# MGC3130_Board.net
KiCad netlist of a schematic drawn in EAGLE
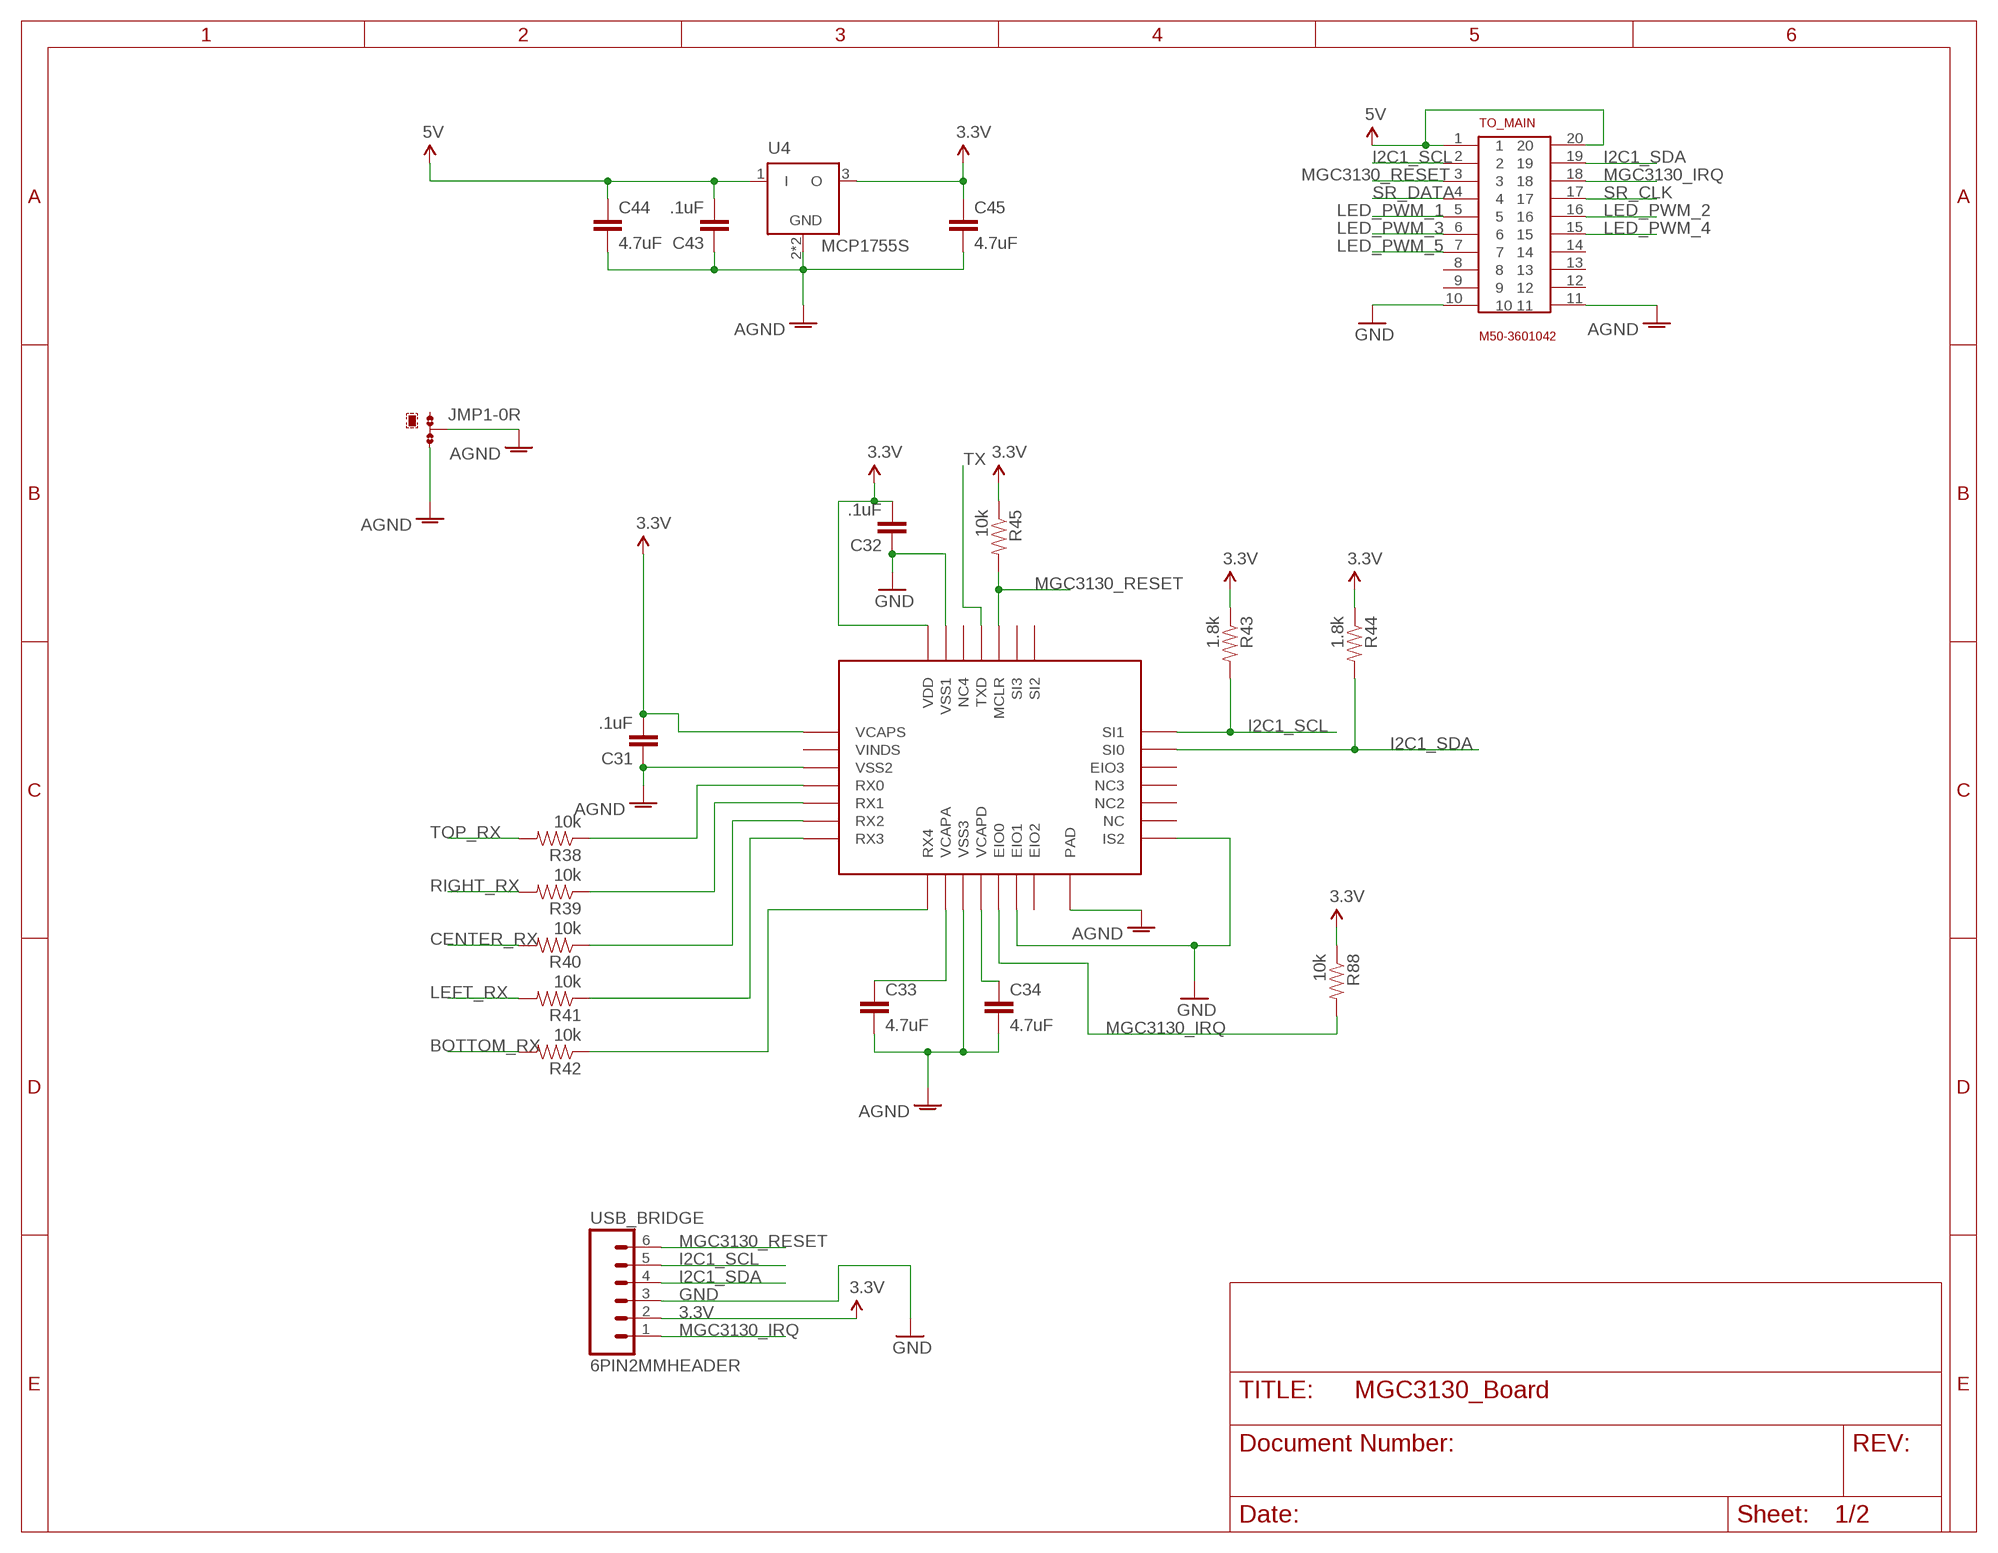
[diagram p0: schematic, sheet 1]
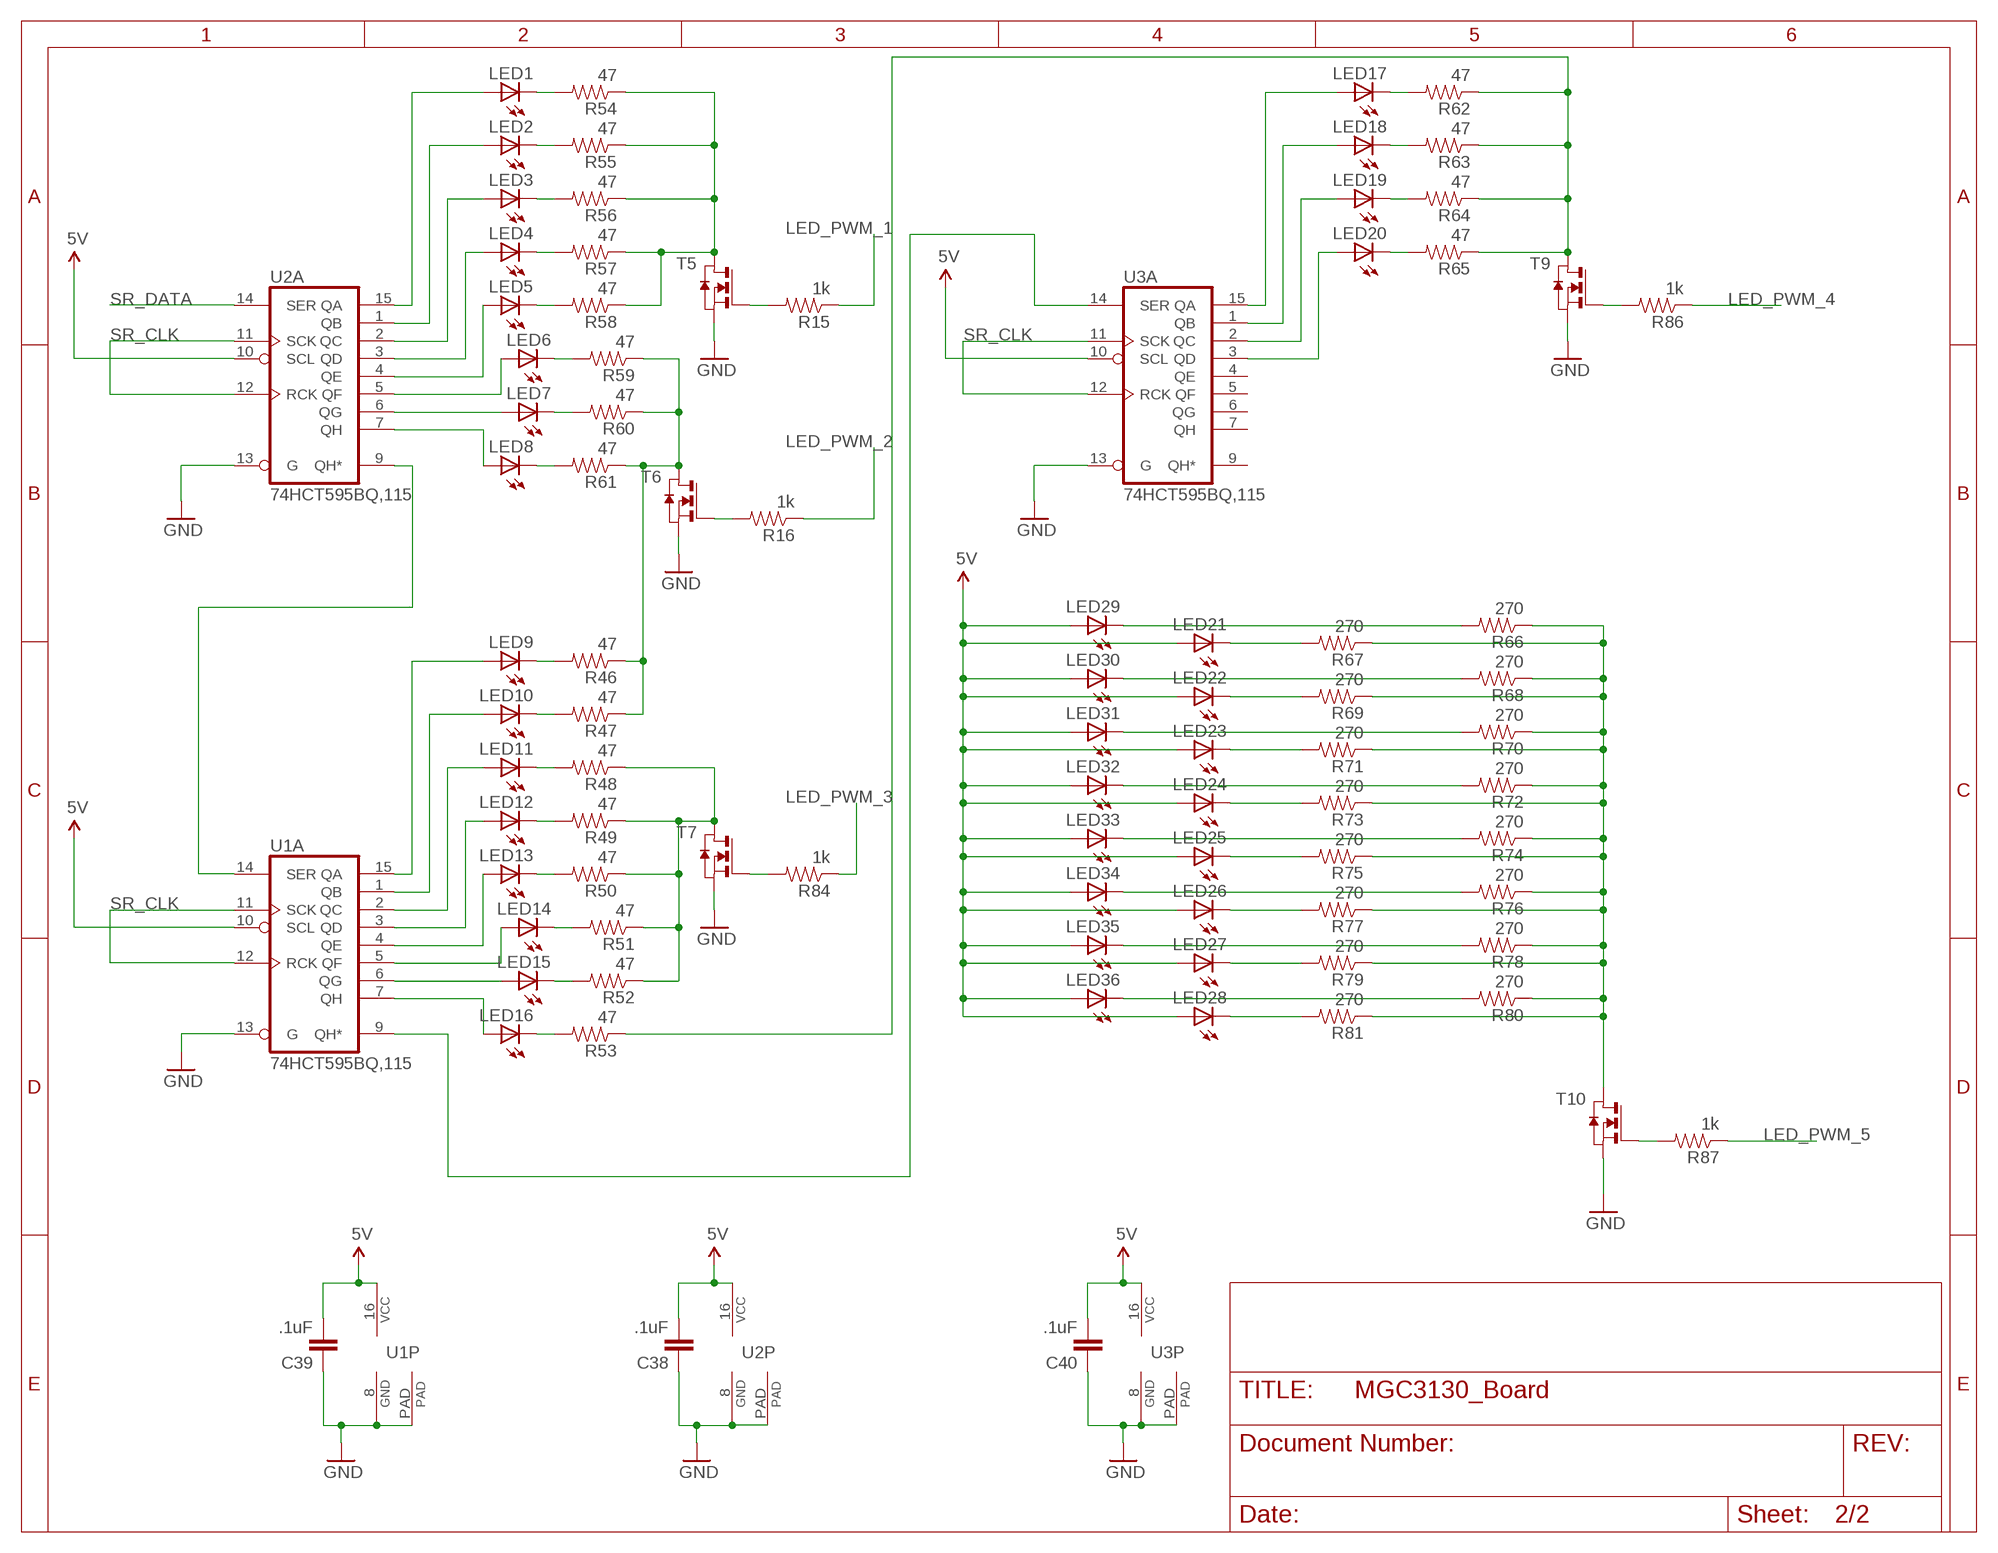
[diagram p1: schematic, sheet 2]

(export (version "E")
  (design (tool "Eeschema 10.0.6"))
  (components
    (comp (ref "C31")
      (value ".1uF")
      (footprint "eagle-import:0603-CAP")
      (libsource (lib "eagle-import") (part "SparkFun-Passives_CAP0603-CAP"))
    )
    (comp (ref "C32")
      (value ".1uF")
      (footprint "eagle-import:0603-CAP")
      (libsource (lib "eagle-import") (part "SparkFun-Passives_CAP0603-CAP"))
    )
    (comp (ref "C33")
      (value "4.7uF")
      (footprint "eagle-import:1206")
      (libsource (lib "eagle-import") (part "CAP1206"))
    )
    (comp (ref "C34")
      (value "4.7uF")
      (footprint "eagle-import:1206")
      (libsource (lib "eagle-import") (part "CAP1206"))
    )
    (comp (ref "C43")
      (value ".1uF")
      (footprint "eagle-import:0603-CAP")
      (libsource (lib "eagle-import") (part "SparkFun-Passives_CAP0603-CAP"))
    )
    (comp (ref "C44")
      (value "4.7uF")
      (footprint "eagle-import:1206")
      (libsource (lib "eagle-import") (part "CAP1206"))
    )
    (comp (ref "C45")
      (value "4.7uF")
      (footprint "eagle-import:1206")
      (libsource (lib "eagle-import") (part "CAP1206"))
    )
    (comp (ref "JMP1")
      (value "0R-JUMPA")
      (footprint "eagle-import:A0R-JMP")
      (libsource (lib "eagle-import") (part "0R-JUMPA"))
    )
    (comp (ref "R38")
      (value "10k")
      (footprint "eagle-import:0603-RES")
      (libsource (lib "eagle-import") (part "RESISTOR0603-RES"))
    )
    (comp (ref "R39")
      (value "10k")
      (footprint "eagle-import:0603-RES")
      (libsource (lib "eagle-import") (part "RESISTOR0603-RES"))
    )
    (comp (ref "R40")
      (value "10k")
      (footprint "eagle-import:0603-RES")
      (libsource (lib "eagle-import") (part "RESISTOR0603-RES"))
    )
    (comp (ref "R41")
      (value "10k")
      (footprint "eagle-import:0603-RES")
      (libsource (lib "eagle-import") (part "RESISTOR0603-RES"))
    )
    (comp (ref "R42")
      (value "10k")
      (footprint "eagle-import:0603-RES")
      (libsource (lib "eagle-import") (part "RESISTOR0603-RES"))
    )
    (comp (ref "R43")
      (value "1.8k")
      (footprint "eagle-import:0603-RES")
      (libsource (lib "eagle-import") (part "RESISTOR0603-RES"))
    )
    (comp (ref "R44")
      (value "1.8k")
      (footprint "eagle-import:0603-RES")
      (libsource (lib "eagle-import") (part "RESISTOR0603-RES"))
    )
    (comp (ref "R45")
      (value "10k")
      (footprint "eagle-import:0603-RES")
      (libsource (lib "eagle-import") (part "RESISTOR0603-RES"))
    )
    (comp (ref "R88")
      (value "10k")
      (footprint "eagle-import:0603-RES")
      (libsource (lib "eagle-import") (part "RESISTOR0603-RES"))
    )
    (comp (ref "TO_MAIN")
      (value "M50-3601042")
      (footprint "eagle-import:M50-3601042")
      (libsource (lib "eagle-import") (part "M50-3601042"))
    )
    (comp (ref "U4")
      (value "MCP1755S")
      (footprint "eagle-import:SOT223")
      (libsource (lib "eagle-import") (part "MCP1755S"))
    )
    (comp (ref "U14")
      (value "MGC3130")
      (footprint "eagle-import:QFN28")
      (libsource (lib "eagle-import") (part "MGC3130"))
    )
    (comp (ref "USB_BRIDGE")
      (value "6PIN2MMHEADER")
      (footprint "eagle-import:1X06_SMD_STRAIGHT")
      (libsource (lib "eagle-import") (part "6PIN2MMHEADER"))
    )
    (comp (ref "C38")
      (value ".1uF")
      (footprint "eagle-import:0603-CAP")
      (libsource (lib "eagle-import") (part "SparkFun-Passives_CAP0603-CAP"))
    )
    (comp (ref "C39")
      (value ".1uF")
      (footprint "eagle-import:0603-CAP")
      (libsource (lib "eagle-import") (part "SparkFun-Passives_CAP0603-CAP"))
    )
    (comp (ref "C40")
      (value ".1uF")
      (footprint "eagle-import:0603-CAP")
      (libsource (lib "eagle-import") (part "SparkFun-Passives_CAP0603-CAP"))
    )
    (comp (ref "LED1")
      (value "APA3010QBC/D-GX")
      (footprint "eagle-import:APA3010")
      (libsource (lib "eagle-import") (part "APA3010QBC/D-GX"))
    )
    (comp (ref "LED2")
      (value "APA3010QBC/D-GX")
      (footprint "eagle-import:APA3010")
      (libsource (lib "eagle-import") (part "APA3010QBC/D-GX"))
    )
    (comp (ref "LED3")
      (value "APA3010QBC/D-GX")
      (footprint "eagle-import:APA3010")
      (libsource (lib "eagle-import") (part "APA3010QBC/D-GX"))
    )
    (comp (ref "LED4")
      (value "APA3010QBC/D-GX")
      (footprint "eagle-import:APA3010")
      (libsource (lib "eagle-import") (part "APA3010QBC/D-GX"))
    )
    (comp (ref "LED5")
      (value "APA3010QBC/D-GX")
      (footprint "eagle-import:APA3010")
      (libsource (lib "eagle-import") (part "APA3010QBC/D-GX"))
    )
    (comp (ref "LED6")
      (value "APA3010QBC/D-GX")
      (footprint "eagle-import:APA3010")
      (libsource (lib "eagle-import") (part "APA3010QBC/D-GX"))
    )
    (comp (ref "LED7")
      (value "APA3010QBC/D-GX")
      (footprint "eagle-import:APA3010")
      (libsource (lib "eagle-import") (part "APA3010QBC/D-GX"))
    )
    (comp (ref "LED8")
      (value "APA3010QBC/D-GX")
      (footprint "eagle-import:APA3010")
      (libsource (lib "eagle-import") (part "APA3010QBC/D-GX"))
    )
    (comp (ref "LED9")
      (value "APA3010QBC/D-GX")
      (footprint "eagle-import:APA3010")
      (libsource (lib "eagle-import") (part "APA3010QBC/D-GX"))
    )
    (comp (ref "LED10")
      (value "APA3010QBC/D-GX")
      (footprint "eagle-import:APA3010")
      (libsource (lib "eagle-import") (part "APA3010QBC/D-GX"))
    )
    (comp (ref "LED11")
      (value "APA3010QBC/D-GX")
      (footprint "eagle-import:APA3010")
      (libsource (lib "eagle-import") (part "APA3010QBC/D-GX"))
    )
    (comp (ref "LED12")
      (value "APA3010QBC/D-GX")
      (footprint "eagle-import:APA3010")
      (libsource (lib "eagle-import") (part "APA3010QBC/D-GX"))
    )
    (comp (ref "LED13")
      (value "APA3010QBC/D-GX")
      (footprint "eagle-import:APA3010")
      (libsource (lib "eagle-import") (part "APA3010QBC/D-GX"))
    )
    (comp (ref "LED14")
      (value "APA3010QBC/D-GX")
      (footprint "eagle-import:APA3010")
      (libsource (lib "eagle-import") (part "APA3010QBC/D-GX"))
    )
    (comp (ref "LED15")
      (value "APA3010QBC/D-GX")
      (footprint "eagle-import:APA3010")
      (libsource (lib "eagle-import") (part "APA3010QBC/D-GX"))
    )
    (comp (ref "LED16")
      (value "APA3010QBC/D-GX")
      (footprint "eagle-import:APA3010")
      (libsource (lib "eagle-import") (part "APA3010QBC/D-GX"))
    )
    (comp (ref "LED17")
      (value "APA3010QBC/D-GX")
      (footprint "eagle-import:APA3010")
      (libsource (lib "eagle-import") (part "APA3010QBC/D-GX"))
    )
    (comp (ref "LED18")
      (value "APA3010QBC/D-GX")
      (footprint "eagle-import:APA3010")
      (libsource (lib "eagle-import") (part "APA3010QBC/D-GX"))
    )
    (comp (ref "LED19")
      (value "APA3010QBC/D-GX")
      (footprint "eagle-import:APA3010")
      (libsource (lib "eagle-import") (part "APA3010QBC/D-GX"))
    )
    (comp (ref "LED20")
      (value "APA3010QBC/D-GX")
      (footprint "eagle-import:APA3010")
      (libsource (lib "eagle-import") (part "APA3010QBC/D-GX"))
    )
    (comp (ref "LED21")
      (value "APA3010SRCPRV-GX")
      (footprint "eagle-import:APA3010")
      (libsource (lib "eagle-import") (part "APA3010SRCPRV-GX"))
    )
    (comp (ref "LED22")
      (value "APA3010SRCPRV-GX")
      (footprint "eagle-import:APA3010")
      (libsource (lib "eagle-import") (part "APA3010SRCPRV-GX"))
    )
    (comp (ref "LED23")
      (value "APA3010SRCPRV-GX")
      (footprint "eagle-import:APA3010")
      (libsource (lib "eagle-import") (part "APA3010SRCPRV-GX"))
    )
    (comp (ref "LED24")
      (value "APA3010SRCPRV-GX")
      (footprint "eagle-import:APA3010")
      (libsource (lib "eagle-import") (part "APA3010SRCPRV-GX"))
    )
    (comp (ref "LED25")
      (value "APA3010SRCPRV-GX")
      (footprint "eagle-import:APA3010")
      (libsource (lib "eagle-import") (part "APA3010SRCPRV-GX"))
    )
    (comp (ref "LED26")
      (value "APA3010SRCPRV-GX")
      (footprint "eagle-import:APA3010")
      (libsource (lib "eagle-import") (part "APA3010SRCPRV-GX"))
    )
    (comp (ref "LED27")
      (value "APA3010SRCPRV-GX")
      (footprint "eagle-import:APA3010")
      (libsource (lib "eagle-import") (part "APA3010SRCPRV-GX"))
    )
    (comp (ref "LED28")
      (value "APA3010SRCPRV-GX")
      (footprint "eagle-import:APA3010")
      (libsource (lib "eagle-import") (part "APA3010SRCPRV-GX"))
    )
    (comp (ref "LED29")
      (value "APA3010SRCPRV-GX")
      (footprint "eagle-import:APA3010")
      (libsource (lib "eagle-import") (part "APA3010SRCPRV-GX"))
    )
    (comp (ref "LED30")
      (value "APA3010SRCPRV-GX")
      (footprint "eagle-import:APA3010")
      (libsource (lib "eagle-import") (part "APA3010SRCPRV-GX"))
    )
    (comp (ref "LED31")
      (value "APA3010SRCPRV-GX")
      (footprint "eagle-import:APA3010")
      (libsource (lib "eagle-import") (part "APA3010SRCPRV-GX"))
    )
    (comp (ref "LED32")
      (value "APA3010SRCPRV-GX")
      (footprint "eagle-import:APA3010")
      (libsource (lib "eagle-import") (part "APA3010SRCPRV-GX"))
    )
    (comp (ref "LED33")
      (value "APA3010SRCPRV-GX")
      (footprint "eagle-import:APA3010")
      (libsource (lib "eagle-import") (part "APA3010SRCPRV-GX"))
    )
    (comp (ref "LED34")
      (value "APA3010SRCPRV-GX")
      (footprint "eagle-import:APA3010")
      (libsource (lib "eagle-import") (part "APA3010SRCPRV-GX"))
    )
    (comp (ref "LED35")
      (value "APA3010SRCPRV-GX")
      (footprint "eagle-import:APA3010")
      (libsource (lib "eagle-import") (part "APA3010SRCPRV-GX"))
    )
    (comp (ref "LED36")
      (value "APA3010SRCPRV-GX")
      (footprint "eagle-import:APA3010")
      (libsource (lib "eagle-import") (part "APA3010SRCPRV-GX"))
    )
    (comp (ref "R15")
      (value "1k")
      (footprint "eagle-import:0603-RES")
      (libsource (lib "eagle-import") (part "RESISTOR0603-RES"))
    )
    (comp (ref "R16")
      (value "1k")
      (footprint "eagle-import:0603-RES")
      (libsource (lib "eagle-import") (part "RESISTOR0603-RES"))
    )
    (comp (ref "R46")
      (value "47")
      (footprint "eagle-import:0603-RES")
      (libsource (lib "eagle-import") (part "RESISTOR0603-RES"))
    )
    (comp (ref "R47")
      (value "47")
      (footprint "eagle-import:0603-RES")
      (libsource (lib "eagle-import") (part "RESISTOR0603-RES"))
    )
    (comp (ref "R48")
      (value "47")
      (footprint "eagle-import:0603-RES")
      (libsource (lib "eagle-import") (part "RESISTOR0603-RES"))
    )
    (comp (ref "R49")
      (value "47")
      (footprint "eagle-import:0603-RES")
      (libsource (lib "eagle-import") (part "RESISTOR0603-RES"))
    )
    (comp (ref "R50")
      (value "47")
      (footprint "eagle-import:0603-RES")
      (libsource (lib "eagle-import") (part "RESISTOR0603-RES"))
    )
    (comp (ref "R51")
      (value "47")
      (footprint "eagle-import:0603-RES")
      (libsource (lib "eagle-import") (part "RESISTOR0603-RES"))
    )
    (comp (ref "R52")
      (value "47")
      (footprint "eagle-import:0603-RES")
      (libsource (lib "eagle-import") (part "RESISTOR0603-RES"))
    )
    (comp (ref "R53")
      (value "47")
      (footprint "eagle-import:0603-RES")
      (libsource (lib "eagle-import") (part "RESISTOR0603-RES"))
    )
    (comp (ref "R54")
      (value "47")
      (footprint "eagle-import:0603-RES")
      (libsource (lib "eagle-import") (part "RESISTOR0603-RES"))
    )
    (comp (ref "R55")
      (value "47")
      (footprint "eagle-import:0603-RES")
      (libsource (lib "eagle-import") (part "RESISTOR0603-RES"))
    )
    (comp (ref "R56")
      (value "47")
      (footprint "eagle-import:0603-RES")
      (libsource (lib "eagle-import") (part "RESISTOR0603-RES"))
    )
    (comp (ref "R57")
      (value "47")
      (footprint "eagle-import:0603-RES")
      (libsource (lib "eagle-import") (part "RESISTOR0603-RES"))
    )
    (comp (ref "R58")
      (value "47")
      (footprint "eagle-import:0603-RES")
      (libsource (lib "eagle-import") (part "RESISTOR0603-RES"))
    )
    (comp (ref "R59")
      (value "47")
      (footprint "eagle-import:0603-RES")
      (libsource (lib "eagle-import") (part "RESISTOR0603-RES"))
    )
    (comp (ref "R60")
      (value "47")
      (footprint "eagle-import:0603-RES")
      (libsource (lib "eagle-import") (part "RESISTOR0603-RES"))
    )
    (comp (ref "R61")
      (value "47")
      (footprint "eagle-import:0603-RES")
      (libsource (lib "eagle-import") (part "RESISTOR0603-RES"))
    )
    (comp (ref "R62")
      (value "47")
      (footprint "eagle-import:0603-RES")
      (libsource (lib "eagle-import") (part "RESISTOR0603-RES"))
    )
    (comp (ref "R63")
      (value "47")
      (footprint "eagle-import:0603-RES")
      (libsource (lib "eagle-import") (part "RESISTOR0603-RES"))
    )
    (comp (ref "R64")
      (value "47")
      (footprint "eagle-import:0603-RES")
      (libsource (lib "eagle-import") (part "RESISTOR0603-RES"))
    )
    (comp (ref "R65")
      (value "47")
      (footprint "eagle-import:0603-RES")
      (libsource (lib "eagle-import") (part "RESISTOR0603-RES"))
    )
    (comp (ref "R66")
      (value "270")
      (footprint "eagle-import:0603-RES")
      (libsource (lib "eagle-import") (part "RESISTOR0603-RES"))
    )
    (comp (ref "R67")
      (value "270")
      (footprint "eagle-import:0603-RES")
      (libsource (lib "eagle-import") (part "RESISTOR0603-RES"))
    )
    (comp (ref "R68")
      (value "270")
      (footprint "eagle-import:0603-RES")
      (libsource (lib "eagle-import") (part "RESISTOR0603-RES"))
    )
    (comp (ref "R69")
      (value "270")
      (footprint "eagle-import:0603-RES")
      (libsource (lib "eagle-import") (part "RESISTOR0603-RES"))
    )
    (comp (ref "R70")
      (value "270")
      (footprint "eagle-import:0603-RES")
      (libsource (lib "eagle-import") (part "RESISTOR0603-RES"))
    )
    (comp (ref "R71")
      (value "270")
      (footprint "eagle-import:0603-RES")
      (libsource (lib "eagle-import") (part "RESISTOR0603-RES"))
    )
    (comp (ref "R72")
      (value "270")
      (footprint "eagle-import:0603-RES")
      (libsource (lib "eagle-import") (part "RESISTOR0603-RES"))
    )
    (comp (ref "R73")
      (value "270")
      (footprint "eagle-import:0603-RES")
      (libsource (lib "eagle-import") (part "RESISTOR0603-RES"))
    )
    (comp (ref "R74")
      (value "270")
      (footprint "eagle-import:0603-RES")
      (libsource (lib "eagle-import") (part "RESISTOR0603-RES"))
    )
    (comp (ref "R75")
      (value "270")
      (footprint "eagle-import:0603-RES")
      (libsource (lib "eagle-import") (part "RESISTOR0603-RES"))
    )
    (comp (ref "R76")
      (value "270")
      (footprint "eagle-import:0603-RES")
      (libsource (lib "eagle-import") (part "RESISTOR0603-RES"))
    )
    (comp (ref "R77")
      (value "270")
      (footprint "eagle-import:0603-RES")
      (libsource (lib "eagle-import") (part "RESISTOR0603-RES"))
    )
    (comp (ref "R78")
      (value "270")
      (footprint "eagle-import:0603-RES")
      (libsource (lib "eagle-import") (part "RESISTOR0603-RES"))
    )
    (comp (ref "R79")
      (value "270")
      (footprint "eagle-import:0603-RES")
      (libsource (lib "eagle-import") (part "RESISTOR0603-RES"))
    )
    (comp (ref "R80")
      (value "270")
      (footprint "eagle-import:0603-RES")
      (libsource (lib "eagle-import") (part "RESISTOR0603-RES"))
    )
    (comp (ref "R81")
      (value "270")
      (footprint "eagle-import:0603-RES")
      (libsource (lib "eagle-import") (part "RESISTOR0603-RES"))
    )
    (comp (ref "R84")
      (value "1k")
      (footprint "eagle-import:0603-RES")
      (libsource (lib "eagle-import") (part "RESISTOR0603-RES"))
    )
    (comp (ref "R86")
      (value "1k")
      (footprint "eagle-import:0603-RES")
      (libsource (lib "eagle-import") (part "RESISTOR0603-RES"))
    )
    (comp (ref "R87")
      (value "1k")
      (footprint "eagle-import:0603-RES")
      (libsource (lib "eagle-import") (part "RESISTOR0603-RES"))
    )
    (comp (ref "T5")
      (value "NMOSSOT23")
      (footprint "eagle-import:SOT-23")
      (libsource (lib "eagle-import") (part "NMOSSOT23"))
    )
    (comp (ref "T6")
      (value "NMOSSOT23")
      (footprint "eagle-import:SOT-23")
      (libsource (lib "eagle-import") (part "NMOSSOT23"))
    )
    (comp (ref "T7")
      (value "NMOSSOT23")
      (footprint "eagle-import:SOT-23")
      (libsource (lib "eagle-import") (part "NMOSSOT23"))
    )
    (comp (ref "T9")
      (value "NMOSSOT23")
      (footprint "eagle-import:SOT-23")
      (libsource (lib "eagle-import") (part "NMOSSOT23"))
    )
    (comp (ref "T10")
      (value "NMOSSOT23")
      (footprint "eagle-import:SOT-23")
      (libsource (lib "eagle-import") (part "NMOSSOT23"))
    )
    (comp (ref "U1")
      (value "74HCT595BQ,115")
      (footprint "eagle-import:DHVQFN16")
      (libsource (lib "eagle-import") (part "74HCT595BQ,115"))
    )
    (comp (ref "U2")
      (value "74HCT595BQ,115")
      (footprint "eagle-import:DHVQFN16")
      (libsource (lib "eagle-import") (part "74HCT595BQ,115"))
    )
    (comp (ref "U3")
      (value "74HCT595BQ,115")
      (footprint "eagle-import:DHVQFN16")
      (libsource (lib "eagle-import") (part "74HCT595BQ,115"))
    )
  )
  (nets
    (net (code "1") (name "3.3V") (class "Default")
      (node (ref "C31") (pin "2") (pinfunction "2_2") (pintype "passive"))
      (node (ref "C32") (pin "2") (pinfunction "2_2") (pintype "passive"))
      (node (ref "C45") (pin "1") (pinfunction "1_1") (pintype "passive"))
      (node (ref "R43") (pin "1") (pinfunction "1_1") (pintype "passive"))
      (node (ref "R44") (pin "1") (pinfunction "1_1") (pintype "passive"))
      (node (ref "R45") (pin "1") (pinfunction "1_1") (pintype "passive"))
      (node (ref "R88") (pin "1") (pinfunction "1_1") (pintype "passive"))
      (node (ref "U14") (pin "P$1") (pinfunction "VCAPS_P$1") (pintype "bidirectional"))
      (node (ref "U14") (pin "P$28") (pinfunction "VDD_P$28") (pintype "bidirectional"))
      (node (ref "U4") (pin "3") (pinfunction "O_3") (pintype "input"))
      (node (ref "USB_BRIDGE") (pin "2") (pinfunction "2_2") (pintype "passive"))
    )
    (net (code "2") (name "5V") (class "Default")
      (node (ref "C38") (pin "2") (pinfunction "2_2") (pintype "passive"))
      (node (ref "C39") (pin "2") (pinfunction "2_2") (pintype "passive"))
      (node (ref "C40") (pin "2") (pinfunction "2_2") (pintype "passive"))
      (node (ref "C43") (pin "2") (pinfunction "2_2") (pintype "passive"))
      (node (ref "C44") (pin "1") (pinfunction "1_1") (pintype "passive"))
      (node (ref "LED21") (pin "P$2") (pinfunction "A_P$2") (pintype "passive"))
      (node (ref "LED22") (pin "P$2") (pinfunction "A_P$2") (pintype "passive"))
      (node (ref "LED23") (pin "P$2") (pinfunction "A_P$2") (pintype "passive"))
      (node (ref "LED24") (pin "P$2") (pinfunction "A_P$2") (pintype "passive"))
      (node (ref "LED25") (pin "P$2") (pinfunction "A_P$2") (pintype "passive"))
      (node (ref "LED26") (pin "P$2") (pinfunction "A_P$2") (pintype "passive"))
      (node (ref "LED27") (pin "P$2") (pinfunction "A_P$2") (pintype "passive"))
      (node (ref "LED28") (pin "P$2") (pinfunction "A_P$2") (pintype "passive"))
      (node (ref "LED29") (pin "P$2") (pinfunction "A_P$2") (pintype "passive"))
      (node (ref "LED30") (pin "P$2") (pinfunction "A_P$2") (pintype "passive"))
      (node (ref "LED31") (pin "P$2") (pinfunction "A_P$2") (pintype "passive"))
      (node (ref "LED32") (pin "P$2") (pinfunction "A_P$2") (pintype "passive"))
      (node (ref "LED33") (pin "P$2") (pinfunction "A_P$2") (pintype "passive"))
      (node (ref "LED34") (pin "P$2") (pinfunction "A_P$2") (pintype "passive"))
      (node (ref "LED35") (pin "P$2") (pinfunction "A_P$2") (pintype "passive"))
      (node (ref "LED36") (pin "P$2") (pinfunction "A_P$2") (pintype "passive"))
      (node (ref "TO_MAIN") (pin "1") (pinfunction "1_1") (pintype "bidirectional"))
      (node (ref "TO_MAIN") (pin "20") (pinfunction "20_20") (pintype "bidirectional"))
      (node (ref "U1") (pin "10") (pinfunction "SCL_10") (pintype "input"))
      (node (ref "U1") (pin "16") (pinfunction "VCC_16") (pintype "power_in"))
      (node (ref "U2") (pin "10") (pinfunction "SCL_10") (pintype "input"))
      (node (ref "U2") (pin "16") (pinfunction "VCC_16") (pintype "power_in"))
      (node (ref "U3") (pin "10") (pinfunction "SCL_10") (pintype "input"))
      (node (ref "U3") (pin "16") (pinfunction "VCC_16") (pintype "power_in"))
      (node (ref "U4") (pin "1") (pinfunction "I_1") (pintype "input"))
    )
    (net (code "3") (name "AGND") (class "Default")
      (node (ref "C31") (pin "1") (pinfunction "1_1") (pintype "passive"))
      (node (ref "C33") (pin "2") (pinfunction "2_2") (pintype "passive"))
      (node (ref "C34") (pin "2") (pinfunction "2_2") (pintype "passive"))
      (node (ref "C43") (pin "1") (pinfunction "1_1") (pintype "passive"))
      (node (ref "C44") (pin "2") (pinfunction "2_2") (pintype "passive"))
      (node (ref "C45") (pin "2") (pinfunction "2_2") (pintype "passive"))
      (node (ref "JMP1") (pin "2") (pinfunction "2_2") (pintype "passive"))
      (node (ref "JMP1") (pin "3") (pinfunction "3_3") (pintype "passive"))
      (node (ref "TO_MAIN") (pin "11") (pinfunction "11_11") (pintype "bidirectional"))
      (node (ref "U14") (pin "P$10") (pinfunction "VSS3_P$10") (pintype "bidirectional"))
      (node (ref "U14") (pin "P$29") (pinfunction "PAD_P$29") (pintype "bidirectional"))
      (node (ref "U14") (pin "P$3") (pinfunction "VSS2_P$3") (pintype "bidirectional"))
      (node (ref "U4") (pin "2") (pinfunction "GND_2") (pintype "power_in"))
      (node (ref "U4") (pin "4") (pinfunction "GND_4") (pintype "power_in"))
    )
    (net (code "4") (name "BOTTOM_RX") (class "Default")
      (node (ref "R42") (pin "2") (pinfunction "2_2") (pintype "passive"))
    )
    (net (code "5") (name "CENTER_RX") (class "Default")
      (node (ref "R40") (pin "2") (pinfunction "2_2") (pintype "passive"))
    )
    (net (code "6") (name "GND") (class "Default")
      (node (ref "C32") (pin "1") (pinfunction "1_1") (pintype "passive"))
      (node (ref "C38") (pin "1") (pinfunction "1_1") (pintype "passive"))
      (node (ref "C39") (pin "1") (pinfunction "1_1") (pintype "passive"))
      (node (ref "C40") (pin "1") (pinfunction "1_1") (pintype "passive"))
      (node (ref "T10") (pin "2") (pinfunction "S_2") (pintype "passive"))
      (node (ref "T5") (pin "2") (pinfunction "S_2") (pintype "passive"))
      (node (ref "T6") (pin "2") (pinfunction "S_2") (pintype "passive"))
      (node (ref "T7") (pin "2") (pinfunction "S_2") (pintype "passive"))
      (node (ref "T9") (pin "2") (pinfunction "S_2") (pintype "passive"))
      (node (ref "TO_MAIN") (pin "10") (pinfunction "10_10") (pintype "bidirectional"))
      (node (ref "U1") (pin "13") (pinfunction "G_13") (pintype "input"))
      (node (ref "U1") (pin "8") (pinfunction "GND_8") (pintype "power_in"))
      (node (ref "U1") (pin "PAD") (pinfunction "GND1_PAD") (pintype "power_in"))
      (node (ref "U14") (pin "P$13") (pinfunction "EIO1_P$13") (pintype "bidirectional"))
      (node (ref "U14") (pin "P$15") (pinfunction "IS2_P$15") (pintype "bidirectional"))
      (node (ref "U14") (pin "P$27") (pinfunction "VSS1_P$27") (pintype "bidirectional"))
      (node (ref "U2") (pin "13") (pinfunction "G_13") (pintype "input"))
      (node (ref "U2") (pin "8") (pinfunction "GND_8") (pintype "power_in"))
      (node (ref "U2") (pin "PAD") (pinfunction "GND1_PAD") (pintype "power_in"))
      (node (ref "U3") (pin "13") (pinfunction "G_13") (pintype "input"))
      (node (ref "U3") (pin "8") (pinfunction "GND_8") (pintype "power_in"))
      (node (ref "U3") (pin "PAD") (pinfunction "GND1_PAD") (pintype "power_in"))
      (node (ref "USB_BRIDGE") (pin "3") (pinfunction "3_3") (pintype "passive"))
    )
    (net (code "7") (name "I2C1_SCL") (class "Default")
      (node (ref "R43") (pin "2") (pinfunction "2_2") (pintype "passive"))
      (node (ref "TO_MAIN") (pin "2") (pinfunction "2_2") (pintype "bidirectional"))
      (node (ref "U14") (pin "P$21") (pinfunction "SI1_P$21") (pintype "bidirectional"))
      (node (ref "USB_BRIDGE") (pin "5") (pinfunction "5_5") (pintype "passive"))
    )
    (net (code "8") (name "I2C1_SDA") (class "Default")
      (node (ref "R44") (pin "2") (pinfunction "2_2") (pintype "passive"))
      (node (ref "TO_MAIN") (pin "19") (pinfunction "19_19") (pintype "bidirectional"))
      (node (ref "U14") (pin "P$20") (pinfunction "SI0_P$20") (pintype "bidirectional"))
      (node (ref "USB_BRIDGE") (pin "4") (pinfunction "4_4") (pintype "passive"))
    )
    (net (code "9") (name "LED_PWM_1") (class "Default")
      (node (ref "R15") (pin "1") (pinfunction "1_1") (pintype "passive"))
      (node (ref "TO_MAIN") (pin "5") (pinfunction "5_5") (pintype "bidirectional"))
    )
    (net (code "10") (name "LED_PWM_2") (class "Default")
      (node (ref "R16") (pin "1") (pinfunction "1_1") (pintype "passive"))
      (node (ref "TO_MAIN") (pin "16") (pinfunction "16_16") (pintype "bidirectional"))
    )
    (net (code "11") (name "LED_PWM_3") (class "Default")
      (node (ref "R84") (pin "1") (pinfunction "1_1") (pintype "passive"))
      (node (ref "TO_MAIN") (pin "6") (pinfunction "6_6") (pintype "bidirectional"))
    )
    (net (code "12") (name "LED_PWM_4") (class "Default")
      (node (ref "R86") (pin "1") (pinfunction "1_1") (pintype "passive"))
      (node (ref "TO_MAIN") (pin "15") (pinfunction "15_15") (pintype "bidirectional"))
    )
    (net (code "13") (name "LED_PWM_5") (class "Default")
      (node (ref "R87") (pin "1") (pinfunction "1_1") (pintype "passive"))
      (node (ref "TO_MAIN") (pin "7") (pinfunction "7_7") (pintype "bidirectional"))
    )
    (net (code "14") (name "LEFT_RX") (class "Default")
      (node (ref "R41") (pin "2") (pinfunction "2_2") (pintype "passive"))
    )
    (net (code "15") (name "MGC3130_IRQ") (class "Default")
      (node (ref "R88") (pin "2") (pinfunction "2_2") (pintype "passive"))
      (node (ref "TO_MAIN") (pin "18") (pinfunction "18_18") (pintype "bidirectional"))
      (node (ref "U14") (pin "P$12") (pinfunction "EIO0_P$12") (pintype "bidirectional"))
      (node (ref "USB_BRIDGE") (pin "1") (pinfunction "1_1") (pintype "passive"))
    )
    (net (code "16") (name "MGC3130_RESET") (class "Default")
      (node (ref "R45") (pin "2") (pinfunction "2_2") (pintype "passive"))
      (node (ref "TO_MAIN") (pin "3") (pinfunction "3_3") (pintype "bidirectional"))
      (node (ref "U14") (pin "P$24") (pinfunction "MCLR_P$24") (pintype "bidirectional"))
      (node (ref "USB_BRIDGE") (pin "6") (pinfunction "6_6") (pintype "passive"))
    )
    (net (code "17") (name "Net-(LED1-A)") (class "Default")
      (node (ref "LED1") (pin "P$2") (pinfunction "A_P$2") (pintype "passive"))
      (node (ref "U2") (pin "15") (pinfunction "QA_15") (pintype "tri_state"))
    )
    (net (code "18") (name "Net-(LED1-C)") (class "Default")
      (node (ref "LED1") (pin "P$1") (pinfunction "C_P$1") (pintype "passive"))
      (node (ref "R54") (pin "2") (pinfunction "2_2") (pintype "passive"))
    )
    (net (code "19") (name "Net-(LED2-A)") (class "Default")
      (node (ref "LED2") (pin "P$2") (pinfunction "A_P$2") (pintype "passive"))
      (node (ref "U2") (pin "1") (pinfunction "QB_1") (pintype "tri_state"))
    )
    (net (code "20") (name "Net-(LED2-C)") (class "Default")
      (node (ref "LED2") (pin "P$1") (pinfunction "C_P$1") (pintype "passive"))
      (node (ref "R55") (pin "2") (pinfunction "2_2") (pintype "passive"))
    )
    (net (code "21") (name "Net-(LED3-A)") (class "Default")
      (node (ref "LED3") (pin "P$2") (pinfunction "A_P$2") (pintype "passive"))
      (node (ref "U2") (pin "2") (pinfunction "QC_2") (pintype "tri_state"))
    )
    (net (code "22") (name "Net-(LED3-C)") (class "Default")
      (node (ref "LED3") (pin "P$1") (pinfunction "C_P$1") (pintype "passive"))
      (node (ref "R56") (pin "2") (pinfunction "2_2") (pintype "passive"))
    )
    (net (code "23") (name "Net-(LED4-A)") (class "Default")
      (node (ref "LED4") (pin "P$2") (pinfunction "A_P$2") (pintype "passive"))
      (node (ref "U2") (pin "3") (pinfunction "QD_3") (pintype "tri_state"))
    )
    (net (code "24") (name "Net-(LED4-C)") (class "Default")
      (node (ref "LED4") (pin "P$1") (pinfunction "C_P$1") (pintype "passive"))
      (node (ref "R57") (pin "2") (pinfunction "2_2") (pintype "passive"))
    )
    (net (code "25") (name "Net-(LED5-A)") (class "Default")
      (node (ref "LED5") (pin "P$2") (pinfunction "A_P$2") (pintype "passive"))
      (node (ref "U2") (pin "4") (pinfunction "QE_4") (pintype "tri_state"))
    )
    (net (code "26") (name "Net-(LED5-C)") (class "Default")
      (node (ref "LED5") (pin "P$1") (pinfunction "C_P$1") (pintype "passive"))
      (node (ref "R58") (pin "2") (pinfunction "2_2") (pintype "passive"))
    )
    (net (code "27") (name "Net-(LED6-A)") (class "Default")
      (node (ref "LED6") (pin "P$2") (pinfunction "A_P$2") (pintype "passive"))
      (node (ref "U2") (pin "5") (pinfunction "QF_5") (pintype "tri_state"))
    )
    (net (code "28") (name "Net-(LED6-C)") (class "Default")
      (node (ref "LED6") (pin "P$1") (pinfunction "C_P$1") (pintype "passive"))
      (node (ref "R59") (pin "2") (pinfunction "2_2") (pintype "passive"))
    )
    (net (code "29") (name "Net-(LED7-A)") (class "Default")
      (node (ref "LED7") (pin "P$2") (pinfunction "A_P$2") (pintype "passive"))
      (node (ref "U2") (pin "6") (pinfunction "QG_6") (pintype "tri_state"))
    )
    (net (code "30") (name "Net-(LED7-C)") (class "Default")
      (node (ref "LED7") (pin "P$1") (pinfunction "C_P$1") (pintype "passive"))
      (node (ref "R60") (pin "2") (pinfunction "2_2") (pintype "passive"))
    )
    (net (code "31") (name "Net-(LED8-A)") (class "Default")
      (node (ref "LED8") (pin "P$2") (pinfunction "A_P$2") (pintype "passive"))
      (node (ref "U2") (pin "7") (pinfunction "QH_7") (pintype "tri_state"))
    )
    (net (code "32") (name "Net-(LED8-C)") (class "Default")
      (node (ref "LED8") (pin "P$1") (pinfunction "C_P$1") (pintype "passive"))
      (node (ref "R61") (pin "2") (pinfunction "2_2") (pintype "passive"))
    )
    (net (code "33") (name "Net-(LED9-A)") (class "Default")
      (node (ref "LED9") (pin "P$2") (pinfunction "A_P$2") (pintype "passive"))
      (node (ref "U1") (pin "15") (pinfunction "QA_15") (pintype "tri_state"))
    )
    (net (code "34") (name "Net-(LED9-C)") (class "Default")
      (node (ref "LED9") (pin "P$1") (pinfunction "C_P$1") (pintype "passive"))
      (node (ref "R46") (pin "2") (pinfunction "2_2") (pintype "passive"))
    )
    (net (code "35") (name "Net-(LED10-A)") (class "Default")
      (node (ref "LED10") (pin "P$2") (pinfunction "A_P$2") (pintype "passive"))
      (node (ref "U1") (pin "1") (pinfunction "QB_1") (pintype "tri_state"))
    )
    (net (code "36") (name "Net-(LED10-C)") (class "Default")
      (node (ref "LED10") (pin "P$1") (pinfunction "C_P$1") (pintype "passive"))
      (node (ref "R47") (pin "2") (pinfunction "2_2") (pintype "passive"))
    )
    (net (code "37") (name "Net-(LED11-A)") (class "Default")
      (node (ref "LED11") (pin "P$2") (pinfunction "A_P$2") (pintype "passive"))
      (node (ref "U1") (pin "2") (pinfunction "QC_2") (pintype "tri_state"))
    )
    (net (code "38") (name "Net-(LED11-C)") (class "Default")
      (node (ref "LED11") (pin "P$1") (pinfunction "C_P$1") (pintype "passive"))
      (node (ref "R48") (pin "2") (pinfunction "2_2") (pintype "passive"))
    )
    (net (code "39") (name "Net-(LED12-A)") (class "Default")
      (node (ref "LED12") (pin "P$2") (pinfunction "A_P$2") (pintype "passive"))
      (node (ref "U1") (pin "3") (pinfunction "QD_3") (pintype "tri_state"))
    )
    (net (code "40") (name "Net-(LED12-C)") (class "Default")
      (node (ref "LED12") (pin "P$1") (pinfunction "C_P$1") (pintype "passive"))
      (node (ref "R49") (pin "2") (pinfunction "2_2") (pintype "passive"))
    )
    (net (code "41") (name "Net-(LED13-A)") (class "Default")
      (node (ref "LED13") (pin "P$2") (pinfunction "A_P$2") (pintype "passive"))
      (node (ref "U1") (pin "4") (pinfunction "QE_4") (pintype "tri_state"))
    )
    (net (code "42") (name "Net-(LED13-C)") (class "Default")
      (node (ref "LED13") (pin "P$1") (pinfunction "C_P$1") (pintype "passive"))
      (node (ref "R50") (pin "2") (pinfunction "2_2") (pintype "passive"))
    )
    (net (code "43") (name "Net-(LED14-A)") (class "Default")
      (node (ref "LED14") (pin "P$2") (pinfunction "A_P$2") (pintype "passive"))
      (node (ref "U1") (pin "5") (pinfunction "QF_5") (pintype "tri_state"))
    )
    (net (code "44") (name "Net-(LED14-C)") (class "Default")
      (node (ref "LED14") (pin "P$1") (pinfunction "C_P$1") (pintype "passive"))
      (node (ref "R51") (pin "2") (pinfunction "2_2") (pintype "passive"))
    )
    (net (code "45") (name "Net-(LED15-A)") (class "Default")
      (node (ref "LED15") (pin "P$2") (pinfunction "A_P$2") (pintype "passive"))
      (node (ref "U1") (pin "6") (pinfunction "QG_6") (pintype "tri_state"))
    )
    (net (code "46") (name "Net-(LED15-C)") (class "Default")
      (node (ref "LED15") (pin "P$1") (pinfunction "C_P$1") (pintype "passive"))
      (node (ref "R52") (pin "2") (pinfunction "2_2") (pintype "passive"))
    )
    (net (code "47") (name "Net-(LED16-A)") (class "Default")
      (node (ref "LED16") (pin "P$2") (pinfunction "A_P$2") (pintype "passive"))
      (node (ref "U1") (pin "7") (pinfunction "QH_7") (pintype "tri_state"))
    )
    (net (code "48") (name "Net-(LED16-C)") (class "Default")
      (node (ref "LED16") (pin "P$1") (pinfunction "C_P$1") (pintype "passive"))
      (node (ref "R53") (pin "2") (pinfunction "2_2") (pintype "passive"))
    )
    (net (code "49") (name "Net-(LED17-A)") (class "Default")
      (node (ref "LED17") (pin "P$2") (pinfunction "A_P$2") (pintype "passive"))
      (node (ref "U3") (pin "15") (pinfunction "QA_15") (pintype "tri_state"))
    )
    (net (code "50") (name "Net-(LED17-C)") (class "Default")
      (node (ref "LED17") (pin "P$1") (pinfunction "C_P$1") (pintype "passive"))
      (node (ref "R62") (pin "2") (pinfunction "2_2") (pintype "passive"))
    )
    (net (code "51") (name "Net-(LED18-A)") (class "Default")
      (node (ref "LED18") (pin "P$2") (pinfunction "A_P$2") (pintype "passive"))
      (node (ref "U3") (pin "1") (pinfunction "QB_1") (pintype "tri_state"))
    )
    (net (code "52") (name "Net-(LED18-C)") (class "Default")
      (node (ref "LED18") (pin "P$1") (pinfunction "C_P$1") (pintype "passive"))
      (node (ref "R63") (pin "2") (pinfunction "2_2") (pintype "passive"))
    )
    (net (code "53") (name "Net-(LED19-A)") (class "Default")
      (node (ref "LED19") (pin "P$2") (pinfunction "A_P$2") (pintype "passive"))
      (node (ref "U3") (pin "2") (pinfunction "QC_2") (pintype "tri_state"))
    )
    (net (code "54") (name "Net-(LED19-C)") (class "Default")
      (node (ref "LED19") (pin "P$1") (pinfunction "C_P$1") (pintype "passive"))
      (node (ref "R64") (pin "2") (pinfunction "2_2") (pintype "passive"))
    )
    (net (code "55") (name "Net-(LED20-A)") (class "Default")
      (node (ref "LED20") (pin "P$2") (pinfunction "A_P$2") (pintype "passive"))
      (node (ref "U3") (pin "3") (pinfunction "QD_3") (pintype "tri_state"))
    )
    (net (code "56") (name "Net-(LED20-C)") (class "Default")
      (node (ref "LED20") (pin "P$1") (pinfunction "C_P$1") (pintype "passive"))
      (node (ref "R65") (pin "2") (pinfunction "2_2") (pintype "passive"))
    )
    (net (code "57") (name "Net-(LED21-C)") (class "Default")
      (node (ref "LED21") (pin "P$1") (pinfunction "C_P$1") (pintype "passive"))
      (node (ref "R67") (pin "2") (pinfunction "2_2") (pintype "passive"))
    )
    (net (code "58") (name "Net-(LED22-C)") (class "Default")
      (node (ref "LED22") (pin "P$1") (pinfunction "C_P$1") (pintype "passive"))
      (node (ref "R69") (pin "2") (pinfunction "2_2") (pintype "passive"))
    )
    (net (code "59") (name "Net-(LED23-C)") (class "Default")
      (node (ref "LED23") (pin "P$1") (pinfunction "C_P$1") (pintype "passive"))
      (node (ref "R71") (pin "2") (pinfunction "2_2") (pintype "passive"))
    )
    (net (code "60") (name "Net-(LED24-C)") (class "Default")
      (node (ref "LED24") (pin "P$1") (pinfunction "C_P$1") (pintype "passive"))
      (node (ref "R73") (pin "2") (pinfunction "2_2") (pintype "passive"))
    )
    (net (code "61") (name "Net-(LED25-C)") (class "Default")
      (node (ref "LED25") (pin "P$1") (pinfunction "C_P$1") (pintype "passive"))
      (node (ref "R75") (pin "2") (pinfunction "2_2") (pintype "passive"))
    )
    (net (code "62") (name "Net-(LED26-C)") (class "Default")
      (node (ref "LED26") (pin "P$1") (pinfunction "C_P$1") (pintype "passive"))
      (node (ref "R77") (pin "2") (pinfunction "2_2") (pintype "passive"))
    )
    (net (code "63") (name "Net-(LED27-C)") (class "Default")
      (node (ref "LED27") (pin "P$1") (pinfunction "C_P$1") (pintype "passive"))
      (node (ref "R79") (pin "2") (pinfunction "2_2") (pintype "passive"))
    )
    (net (code "64") (name "Net-(LED28-C)") (class "Default")
      (node (ref "LED28") (pin "P$1") (pinfunction "C_P$1") (pintype "passive"))
      (node (ref "R81") (pin "2") (pinfunction "2_2") (pintype "passive"))
    )
    (net (code "65") (name "Net-(LED29-C)") (class "Default")
      (node (ref "LED29") (pin "P$1") (pinfunction "C_P$1") (pintype "passive"))
      (node (ref "R66") (pin "2") (pinfunction "2_2") (pintype "passive"))
    )
    (net (code "66") (name "Net-(LED30-C)") (class "Default")
      (node (ref "LED30") (pin "P$1") (pinfunction "C_P$1") (pintype "passive"))
      (node (ref "R68") (pin "2") (pinfunction "2_2") (pintype "passive"))
    )
    (net (code "67") (name "Net-(LED31-C)") (class "Default")
      (node (ref "LED31") (pin "P$1") (pinfunction "C_P$1") (pintype "passive"))
      (node (ref "R70") (pin "2") (pinfunction "2_2") (pintype "passive"))
    )
    (net (code "68") (name "Net-(LED32-C)") (class "Default")
      (node (ref "LED32") (pin "P$1") (pinfunction "C_P$1") (pintype "passive"))
      (node (ref "R72") (pin "2") (pinfunction "2_2") (pintype "passive"))
    )
    (net (code "69") (name "Net-(LED33-C)") (class "Default")
      (node (ref "LED33") (pin "P$1") (pinfunction "C_P$1") (pintype "passive"))
      (node (ref "R74") (pin "2") (pinfunction "2_2") (pintype "passive"))
    )
    (net (code "70") (name "Net-(LED34-C)") (class "Default")
      (node (ref "LED34") (pin "P$1") (pinfunction "C_P$1") (pintype "passive"))
      (node (ref "R76") (pin "2") (pinfunction "2_2") (pintype "passive"))
    )
    (net (code "71") (name "Net-(LED35-C)") (class "Default")
      (node (ref "LED35") (pin "P$1") (pinfunction "C_P$1") (pintype "passive"))
      (node (ref "R78") (pin "2") (pinfunction "2_2") (pintype "passive"))
    )
    (net (code "72") (name "Net-(LED36-C)") (class "Default")
      (node (ref "LED36") (pin "P$1") (pinfunction "C_P$1") (pintype "passive"))
      (node (ref "R80") (pin "2") (pinfunction "2_2") (pintype "passive"))
    )
    (net (code "73") (name "Net-(T5-D)") (class "Default")
      (node (ref "R54") (pin "1") (pinfunction "1_1") (pintype "passive"))
      (node (ref "R55") (pin "1") (pinfunction "1_1") (pintype "passive"))
      (node (ref "R56") (pin "1") (pinfunction "1_1") (pintype "passive"))
      (node (ref "R57") (pin "1") (pinfunction "1_1") (pintype "passive"))
      (node (ref "R58") (pin "1") (pinfunction "1_1") (pintype "passive"))
      (node (ref "T5") (pin "1") (pinfunction "D_1") (pintype "passive"))
    )
    (net (code "74") (name "Net-(T5-G)") (class "Default")
      (node (ref "R15") (pin "2") (pinfunction "2_2") (pintype "passive"))
      (node (ref "T5") (pin "3") (pinfunction "G_3") (pintype "passive"))
    )
    (net (code "75") (name "Net-(T6-D)") (class "Default")
      (node (ref "R46") (pin "1") (pinfunction "1_1") (pintype "passive"))
      (node (ref "R47") (pin "1") (pinfunction "1_1") (pintype "passive"))
      (node (ref "R59") (pin "1") (pinfunction "1_1") (pintype "passive"))
      (node (ref "R60") (pin "1") (pinfunction "1_1") (pintype "passive"))
      (node (ref "R61") (pin "1") (pinfunction "1_1") (pintype "passive"))
      (node (ref "T6") (pin "1") (pinfunction "D_1") (pintype "passive"))
    )
    (net (code "76") (name "Net-(T6-G)") (class "Default")
      (node (ref "R16") (pin "2") (pinfunction "2_2") (pintype "passive"))
      (node (ref "T6") (pin "3") (pinfunction "G_3") (pintype "passive"))
    )
    (net (code "77") (name "Net-(T7-D)") (class "Default")
      (node (ref "R48") (pin "1") (pinfunction "1_1") (pintype "passive"))
      (node (ref "R49") (pin "1") (pinfunction "1_1") (pintype "passive"))
      (node (ref "R50") (pin "1") (pinfunction "1_1") (pintype "passive"))
      (node (ref "R51") (pin "1") (pinfunction "1_1") (pintype "passive"))
      (node (ref "R52") (pin "1") (pinfunction "1_1") (pintype "passive"))
      (node (ref "T7") (pin "1") (pinfunction "D_1") (pintype "passive"))
    )
    (net (code "78") (name "Net-(T7-G)") (class "Default")
      (node (ref "R84") (pin "2") (pinfunction "2_2") (pintype "passive"))
      (node (ref "T7") (pin "3") (pinfunction "G_3") (pintype "passive"))
    )
    (net (code "79") (name "Net-(T9-D)") (class "Default")
      (node (ref "R53") (pin "1") (pinfunction "1_1") (pintype "passive"))
      (node (ref "R62") (pin "1") (pinfunction "1_1") (pintype "passive"))
      (node (ref "R63") (pin "1") (pinfunction "1_1") (pintype "passive"))
      (node (ref "R64") (pin "1") (pinfunction "1_1") (pintype "passive"))
      (node (ref "R65") (pin "1") (pinfunction "1_1") (pintype "passive"))
      (node (ref "T9") (pin "1") (pinfunction "D_1") (pintype "passive"))
    )
    (net (code "80") (name "Net-(T9-G)") (class "Default")
      (node (ref "R86") (pin "2") (pinfunction "2_2") (pintype "passive"))
      (node (ref "T9") (pin "3") (pinfunction "G_3") (pintype "passive"))
    )
    (net (code "81") (name "Net-(T10-D)") (class "Default")
      (node (ref "R66") (pin "1") (pinfunction "1_1") (pintype "passive"))
      (node (ref "R67") (pin "1") (pinfunction "1_1") (pintype "passive"))
      (node (ref "R68") (pin "1") (pinfunction "1_1") (pintype "passive"))
      (node (ref "R69") (pin "1") (pinfunction "1_1") (pintype "passive"))
      (node (ref "R70") (pin "1") (pinfunction "1_1") (pintype "passive"))
      (node (ref "R71") (pin "1") (pinfunction "1_1") (pintype "passive"))
      (node (ref "R72") (pin "1") (pinfunction "1_1") (pintype "passive"))
      (node (ref "R73") (pin "1") (pinfunction "1_1") (pintype "passive"))
      (node (ref "R74") (pin "1") (pinfunction "1_1") (pintype "passive"))
      (node (ref "R75") (pin "1") (pinfunction "1_1") (pintype "passive"))
      (node (ref "R76") (pin "1") (pinfunction "1_1") (pintype "passive"))
      (node (ref "R77") (pin "1") (pinfunction "1_1") (pintype "passive"))
      (node (ref "R78") (pin "1") (pinfunction "1_1") (pintype "passive"))
      (node (ref "R79") (pin "1") (pinfunction "1_1") (pintype "passive"))
      (node (ref "R80") (pin "1") (pinfunction "1_1") (pintype "passive"))
      (node (ref "R81") (pin "1") (pinfunction "1_1") (pintype "passive"))
      (node (ref "T10") (pin "1") (pinfunction "D_1") (pintype "passive"))
    )
    (net (code "82") (name "Net-(T10-G)") (class "Default")
      (node (ref "R87") (pin "2") (pinfunction "2_2") (pintype "passive"))
      (node (ref "T10") (pin "3") (pinfunction "G_3") (pintype "passive"))
    )
    (net (code "83") (name "Net-(U1A-QH*)") (class "Default")
      (node (ref "U1") (pin "9") (pinfunction "QH*_9") (pintype "tri_state"))
      (node (ref "U3") (pin "14") (pinfunction "SER_14") (pintype "input"))
    )
    (net (code "84") (name "Net-(U1A-SER)") (class "Default")
      (node (ref "U1") (pin "14") (pinfunction "SER_14") (pintype "input"))
      (node (ref "U2") (pin "9") (pinfunction "QH*_9") (pintype "tri_state"))
    )
    (net (code "85") (name "Net-(U14-RX0)") (class "Default")
      (node (ref "R38") (pin "1") (pinfunction "1_1") (pintype "passive"))
      (node (ref "U14") (pin "P$4") (pinfunction "RX0_P$4") (pintype "bidirectional"))
    )
    (net (code "86") (name "Net-(U14-RX1)") (class "Default")
      (node (ref "R39") (pin "1") (pinfunction "1_1") (pintype "passive"))
      (node (ref "U14") (pin "P$5") (pinfunction "RX1_P$5") (pintype "bidirectional"))
    )
    (net (code "87") (name "Net-(U14-RX2)") (class "Default")
      (node (ref "R40") (pin "1") (pinfunction "1_1") (pintype "passive"))
      (node (ref "U14") (pin "P$6") (pinfunction "RX2_P$6") (pintype "bidirectional"))
    )
    (net (code "88") (name "Net-(U14-RX3)") (class "Default")
      (node (ref "R41") (pin "1") (pinfunction "1_1") (pintype "passive"))
      (node (ref "U14") (pin "P$7") (pinfunction "RX3_P$7") (pintype "bidirectional"))
    )
    (net (code "89") (name "Net-(U14-RX4)") (class "Default")
      (node (ref "R42") (pin "1") (pinfunction "1_1") (pintype "passive"))
      (node (ref "U14") (pin "P$8") (pinfunction "RX4_P$8") (pintype "bidirectional"))
    )
    (net (code "90") (name "Net-(U14-VCAPA)") (class "Default")
      (node (ref "C33") (pin "1") (pinfunction "1_1") (pintype "passive"))
      (node (ref "U14") (pin "P$9") (pinfunction "VCAPA_P$9") (pintype "bidirectional"))
    )
    (net (code "91") (name "Net-(U14-VCAPD)") (class "Default")
      (node (ref "C34") (pin "1") (pinfunction "1_1") (pintype "passive"))
      (node (ref "U14") (pin "P$11") (pinfunction "VCAPD_P$11") (pintype "bidirectional"))
    )
    (net (code "92") (name "RIGHT_RX") (class "Default")
      (node (ref "R39") (pin "2") (pinfunction "2_2") (pintype "passive"))
    )
    (net (code "93") (name "SR_CLK") (class "Default")
      (node (ref "TO_MAIN") (pin "17") (pinfunction "17_17") (pintype "bidirectional"))
      (node (ref "U1") (pin "11") (pinfunction "SCK_11") (pintype "input"))
      (node (ref "U1") (pin "12") (pinfunction "RCK_12") (pintype "input"))
      (node (ref "U2") (pin "11") (pinfunction "SCK_11") (pintype "input"))
      (node (ref "U2") (pin "12") (pinfunction "RCK_12") (pintype "input"))
      (node (ref "U3") (pin "11") (pinfunction "SCK_11") (pintype "input"))
      (node (ref "U3") (pin "12") (pinfunction "RCK_12") (pintype "input"))
    )
    (net (code "94") (name "SR_DATA") (class "Default")
      (node (ref "TO_MAIN") (pin "4") (pinfunction "4_4") (pintype "bidirectional"))
      (node (ref "U2") (pin "14") (pinfunction "SER_14") (pintype "input"))
    )
    (net (code "95") (name "TOP_RX") (class "Default")
      (node (ref "R38") (pin "2") (pinfunction "2_2") (pintype "passive"))
    )
    (net (code "96") (name "TX") (class "Default")
      (node (ref "U14") (pin "P$25") (pinfunction "TXD_P$25") (pintype "bidirectional"))
    )
    (net (code "97") (name "unconnected-(JMP1-Pad1)") (class "Default")
      (node (ref "JMP1") (pin "1") (pinfunction "1_1") (pintype "passive"))
    )
    (net (code "98") (name "unconnected-(TO_MAIN-Pad8)") (class "Default")
      (node (ref "TO_MAIN") (pin "8") (pinfunction "8_8") (pintype "bidirectional"))
    )
    (net (code "99") (name "unconnected-(TO_MAIN-Pad9)") (class "Default")
      (node (ref "TO_MAIN") (pin "9") (pinfunction "9_9") (pintype "bidirectional"))
    )
    (net (code "100") (name "unconnected-(TO_MAIN-Pad12)") (class "Default")
      (node (ref "TO_MAIN") (pin "12") (pinfunction "12_12") (pintype "bidirectional"))
    )
    (net (code "101") (name "unconnected-(TO_MAIN-Pad13)") (class "Default")
      (node (ref "TO_MAIN") (pin "13") (pinfunction "13_13") (pintype "bidirectional"))
    )
    (net (code "102") (name "unconnected-(TO_MAIN-Pad14)") (class "Default")
      (node (ref "TO_MAIN") (pin "14") (pinfunction "14_14") (pintype "bidirectional"))
    )
    (net (code "103") (name "unconnected-(U3A-QE-Pad4)") (class "Default")
      (node (ref "U3") (pin "4") (pinfunction "QE_4") (pintype "tri_state"))
    )
    (net (code "104") (name "unconnected-(U3A-QF-Pad5)") (class "Default")
      (node (ref "U3") (pin "5") (pinfunction "QF_5") (pintype "tri_state"))
    )
    (net (code "105") (name "unconnected-(U3A-QG-Pad6)") (class "Default")
      (node (ref "U3") (pin "6") (pinfunction "QG_6") (pintype "tri_state"))
    )
    (net (code "106") (name "unconnected-(U3A-QH*-Pad9)") (class "Default")
      (node (ref "U3") (pin "9") (pinfunction "QH*_9") (pintype "tri_state"))
    )
    (net (code "107") (name "unconnected-(U3A-QH-Pad7)") (class "Default")
      (node (ref "U3") (pin "7") (pinfunction "QH_7") (pintype "tri_state"))
    )
    (net (code "108") (name "unconnected-(U14-EIO2-PadP$14)") (class "Default")
      (node (ref "U14") (pin "P$14") (pinfunction "EIO2_P$14") (pintype "bidirectional"))
    )
    (net (code "109") (name "unconnected-(U14-EIO3-PadP$19)") (class "Default")
      (node (ref "U14") (pin "P$19") (pinfunction "EIO3_P$19") (pintype "bidirectional"))
    )
    (net (code "110") (name "unconnected-(U14-NC-PadP$16)") (class "Default")
      (node (ref "U14") (pin "P$16") (pinfunction "NC_P$16") (pintype "bidirectional"))
    )
    (net (code "111") (name "unconnected-(U14-NC2-PadP$17)") (class "Default")
      (node (ref "U14") (pin "P$17") (pinfunction "NC2_P$17") (pintype "bidirectional"))
    )
    (net (code "112") (name "unconnected-(U14-NC3-PadP$18)") (class "Default")
      (node (ref "U14") (pin "P$18") (pinfunction "NC3_P$18") (pintype "bidirectional"))
    )
    (net (code "113") (name "unconnected-(U14-NC4-PadP$26)") (class "Default")
      (node (ref "U14") (pin "P$26") (pinfunction "NC4_P$26") (pintype "bidirectional"))
    )
    (net (code "114") (name "unconnected-(U14-SI2-PadP$22)") (class "Default")
      (node (ref "U14") (pin "P$22") (pinfunction "SI2_P$22") (pintype "bidirectional"))
    )
    (net (code "115") (name "unconnected-(U14-SI3-PadP$23)") (class "Default")
      (node (ref "U14") (pin "P$23") (pinfunction "SI3_P$23") (pintype "bidirectional"))
    )
    (net (code "116") (name "unconnected-(U14-VINDS-PadP$2)") (class "Default")
      (node (ref "U14") (pin "P$2") (pinfunction "VINDS_P$2") (pintype "bidirectional"))
    )
  )
)
